# R603X.net
KiCad netlist of a schematic drawn in EAGLE
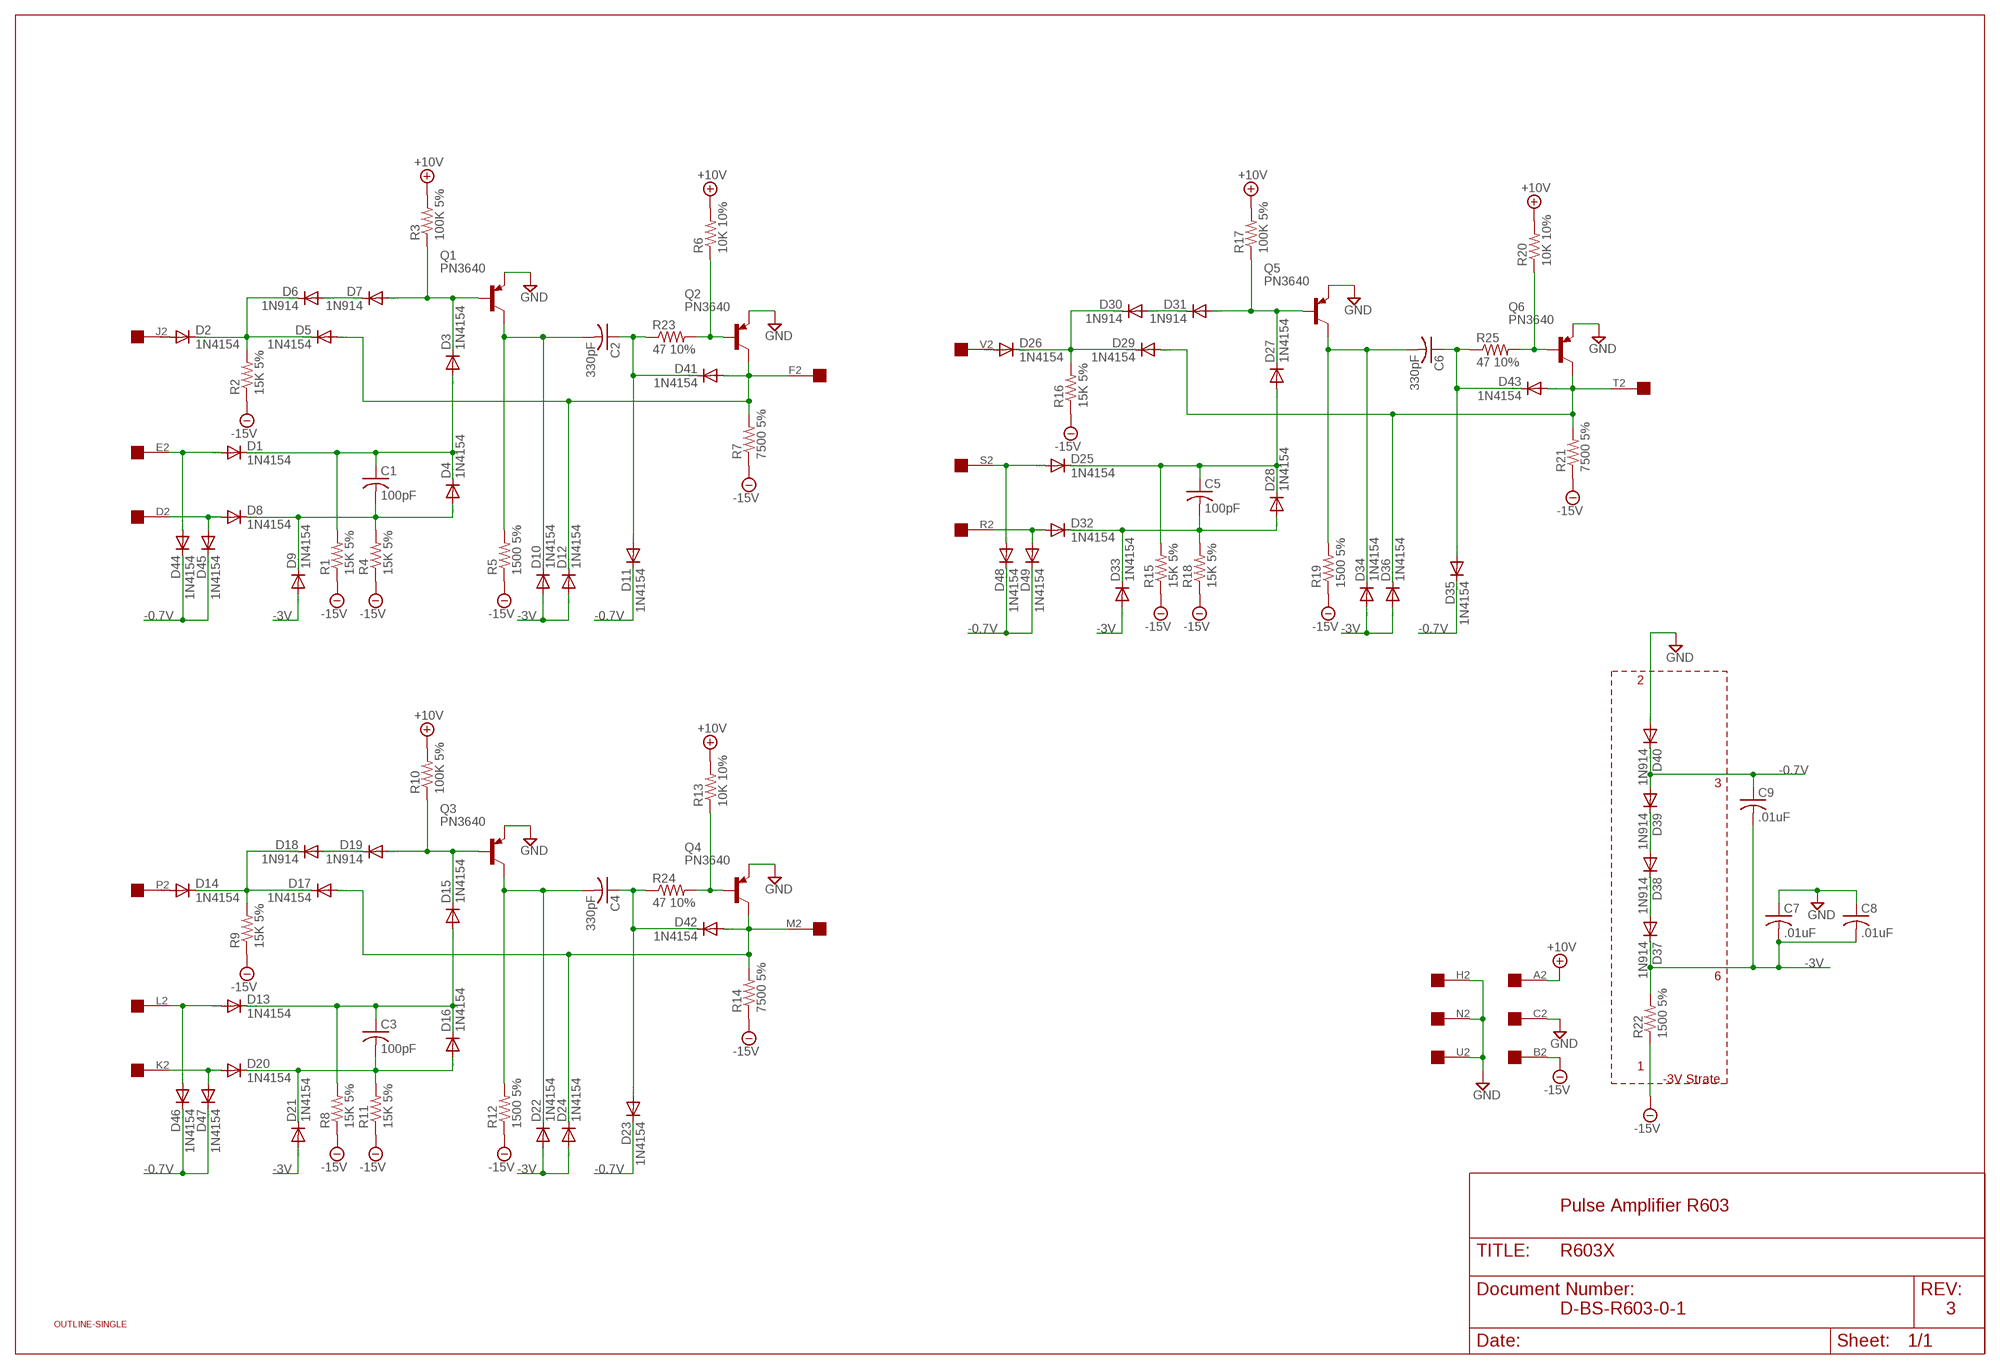
[diagram p0: schematic, sheet 1]

(export (version "E")
  (design (tool "Eeschema 10.0.6"))
  (components
    (comp (ref "C1")
      (value "100pF")
      (footprint "eagle-import:C050-025X075")
      (libsource (lib "eagle-import") (part "C-US050-025X075"))
    )
    (comp (ref "C2")
      (value "330pF")
      (footprint "eagle-import:C050-025X075")
      (libsource (lib "eagle-import") (part "C-US050-025X075"))
    )
    (comp (ref "C3")
      (value "100pF")
      (footprint "eagle-import:C050-025X075")
      (libsource (lib "eagle-import") (part "C-US050-025X075"))
    )
    (comp (ref "C4")
      (value "330pF")
      (footprint "eagle-import:C050-025X075")
      (libsource (lib "eagle-import") (part "C-US050-025X075"))
    )
    (comp (ref "C5")
      (value "100pF")
      (footprint "eagle-import:C050-025X075")
      (libsource (lib "eagle-import") (part "C-US050-025X075"))
    )
    (comp (ref "C6")
      (value "330pF")
      (footprint "eagle-import:C050-025X075")
      (libsource (lib "eagle-import") (part "C-US050-025X075"))
    )
    (comp (ref "C7")
      (value ".01uF")
      (footprint "eagle-import:C050-025X075")
      (libsource (lib "eagle-import") (part "C-US050-025X075"))
    )
    (comp (ref "C8")
      (value ".01uF")
      (footprint "eagle-import:C050-025X075")
      (libsource (lib "eagle-import") (part "C-US050-025X075"))
    )
    (comp (ref "C9")
      (value ".01uF")
      (footprint "eagle-import:C050-025X075")
      (libsource (lib "eagle-import") (part "C-US050-025X075"))
    )
    (comp (ref "D1")
      (value "1N4154")
      (footprint "eagle-import:DO35-10")
      (libsource (lib "eagle-import") (part "1N4148DO35-10"))
    )
    (comp (ref "D2")
      (value "1N4154")
      (footprint "eagle-import:DO35-10")
      (libsource (lib "eagle-import") (part "1N4148DO35-10"))
    )
    (comp (ref "D3")
      (value "1N4154")
      (footprint "eagle-import:DO35-10")
      (libsource (lib "eagle-import") (part "1N4148DO35-10"))
    )
    (comp (ref "D4")
      (value "1N4154")
      (footprint "eagle-import:DO35-10")
      (libsource (lib "eagle-import") (part "1N4148DO35-10"))
    )
    (comp (ref "D5")
      (value "1N4154")
      (footprint "eagle-import:DO35-10")
      (libsource (lib "eagle-import") (part "1N4148DO35-10"))
    )
    (comp (ref "D6")
      (value "1N914")
      (footprint "eagle-import:DO35-10")
      (libsource (lib "eagle-import") (part "1N4148DO35-10"))
    )
    (comp (ref "D7")
      (value "1N914")
      (footprint "eagle-import:DO35-10")
      (libsource (lib "eagle-import") (part "1N4148DO35-10"))
    )
    (comp (ref "D8")
      (value "1N4154")
      (footprint "eagle-import:DO35-10")
      (libsource (lib "eagle-import") (part "1N4148DO35-10"))
    )
    (comp (ref "D9")
      (value "1N4154")
      (footprint "eagle-import:DO35-10")
      (libsource (lib "eagle-import") (part "1N4148DO35-10"))
    )
    (comp (ref "D10")
      (value "1N4154")
      (footprint "eagle-import:DO35-10")
      (libsource (lib "eagle-import") (part "1N4148DO35-10"))
    )
    (comp (ref "D11")
      (value "1N4154")
      (footprint "eagle-import:DO35-10")
      (libsource (lib "eagle-import") (part "1N4148DO35-10"))
    )
    (comp (ref "D12")
      (value "1N4154")
      (footprint "eagle-import:DO35-10")
      (libsource (lib "eagle-import") (part "1N4148DO35-10"))
    )
    (comp (ref "D13")
      (value "1N4154")
      (footprint "eagle-import:DO35-10")
      (libsource (lib "eagle-import") (part "1N4148DO35-10"))
    )
    (comp (ref "D14")
      (value "1N4154")
      (footprint "eagle-import:DO35-10")
      (libsource (lib "eagle-import") (part "1N4148DO35-10"))
    )
    (comp (ref "D15")
      (value "1N4154")
      (footprint "eagle-import:DO35-10")
      (libsource (lib "eagle-import") (part "1N4148DO35-10"))
    )
    (comp (ref "D16")
      (value "1N4154")
      (footprint "eagle-import:DO35-10")
      (libsource (lib "eagle-import") (part "1N4148DO35-10"))
    )
    (comp (ref "D17")
      (value "1N4154")
      (footprint "eagle-import:DO35-10")
      (libsource (lib "eagle-import") (part "1N4148DO35-10"))
    )
    (comp (ref "D18")
      (value "1N914")
      (footprint "eagle-import:DO35-10")
      (libsource (lib "eagle-import") (part "1N4148DO35-10"))
    )
    (comp (ref "D19")
      (value "1N914")
      (footprint "eagle-import:DO35-10")
      (libsource (lib "eagle-import") (part "1N4148DO35-10"))
    )
    (comp (ref "D20")
      (value "1N4154")
      (footprint "eagle-import:DO35-10")
      (libsource (lib "eagle-import") (part "1N4148DO35-10"))
    )
    (comp (ref "D21")
      (value "1N4154")
      (footprint "eagle-import:DO35-10")
      (libsource (lib "eagle-import") (part "1N4148DO35-10"))
    )
    (comp (ref "D22")
      (value "1N4154")
      (footprint "eagle-import:DO35-10")
      (libsource (lib "eagle-import") (part "1N4148DO35-10"))
    )
    (comp (ref "D23")
      (value "1N4154")
      (footprint "eagle-import:DO35-10")
      (libsource (lib "eagle-import") (part "1N4148DO35-10"))
    )
    (comp (ref "D24")
      (value "1N4154")
      (footprint "eagle-import:DO35-10")
      (libsource (lib "eagle-import") (part "1N4148DO35-10"))
    )
    (comp (ref "D25")
      (value "1N4154")
      (footprint "eagle-import:DO35-10")
      (libsource (lib "eagle-import") (part "1N4148DO35-10"))
    )
    (comp (ref "D26")
      (value "1N4154")
      (footprint "eagle-import:DO35-10")
      (libsource (lib "eagle-import") (part "1N4148DO35-10"))
    )
    (comp (ref "D27")
      (value "1N4154")
      (footprint "eagle-import:DO35-10")
      (libsource (lib "eagle-import") (part "1N4148DO35-10"))
    )
    (comp (ref "D28")
      (value "1N4154")
      (footprint "eagle-import:DO35-10")
      (libsource (lib "eagle-import") (part "1N4148DO35-10"))
    )
    (comp (ref "D29")
      (value "1N4154")
      (footprint "eagle-import:DO35-10")
      (libsource (lib "eagle-import") (part "1N4148DO35-10"))
    )
    (comp (ref "D30")
      (value "1N914")
      (footprint "eagle-import:DO35-10")
      (libsource (lib "eagle-import") (part "1N4148DO35-10"))
    )
    (comp (ref "D31")
      (value "1N914")
      (footprint "eagle-import:DO35-10")
      (libsource (lib "eagle-import") (part "1N4148DO35-10"))
    )
    (comp (ref "D32")
      (value "1N4154")
      (footprint "eagle-import:DO35-10")
      (libsource (lib "eagle-import") (part "1N4148DO35-10"))
    )
    (comp (ref "D33")
      (value "1N4154")
      (footprint "eagle-import:DO35-10")
      (libsource (lib "eagle-import") (part "1N4148DO35-10"))
    )
    (comp (ref "D34")
      (value "1N4154")
      (footprint "eagle-import:DO35-10")
      (libsource (lib "eagle-import") (part "1N4148DO35-10"))
    )
    (comp (ref "D35")
      (value "1N4154")
      (footprint "eagle-import:DO35-10")
      (libsource (lib "eagle-import") (part "1N4148DO35-10"))
    )
    (comp (ref "D36")
      (value "1N4154")
      (footprint "eagle-import:DO35-10")
      (libsource (lib "eagle-import") (part "1N4148DO35-10"))
    )
    (comp (ref "D37")
      (value "1N914")
      (footprint "eagle-import:DO35-10")
      (libsource (lib "eagle-import") (part "1N4148DO35-10"))
    )
    (comp (ref "D38")
      (value "1N914")
      (footprint "eagle-import:DO35-10")
      (libsource (lib "eagle-import") (part "1N4148DO35-10"))
    )
    (comp (ref "D39")
      (value "1N914")
      (footprint "eagle-import:DO35-10")
      (libsource (lib "eagle-import") (part "1N4148DO35-10"))
    )
    (comp (ref "D40")
      (value "1N914")
      (footprint "eagle-import:DO35-10")
      (libsource (lib "eagle-import") (part "1N4148DO35-10"))
    )
    (comp (ref "D41")
      (value "1N4154")
      (footprint "eagle-import:DO35-10")
      (libsource (lib "eagle-import") (part "1N4148DO35-10"))
    )
    (comp (ref "D42")
      (value "1N4154")
      (footprint "eagle-import:DO35-10")
      (libsource (lib "eagle-import") (part "1N4148DO35-10"))
    )
    (comp (ref "D43")
      (value "1N4154")
      (footprint "eagle-import:DO35-10")
      (libsource (lib "eagle-import") (part "1N4148DO35-10"))
    )
    (comp (ref "D44")
      (value "1N4154")
      (footprint "eagle-import:DO35-10")
      (libsource (lib "eagle-import") (part "1N4148DO35-10"))
    )
    (comp (ref "D45")
      (value "1N4154")
      (footprint "eagle-import:DO35-10")
      (libsource (lib "eagle-import") (part "1N4148DO35-10"))
    )
    (comp (ref "D46")
      (value "1N4154")
      (footprint "eagle-import:DO35-10")
      (libsource (lib "eagle-import") (part "1N4148DO35-10"))
    )
    (comp (ref "D47")
      (value "1N4154")
      (footprint "eagle-import:DO35-10")
      (libsource (lib "eagle-import") (part "1N4148DO35-10"))
    )
    (comp (ref "D48")
      (value "1N4154")
      (footprint "eagle-import:DO35-10")
      (libsource (lib "eagle-import") (part "1N4148DO35-10"))
    )
    (comp (ref "D49")
      (value "1N4154")
      (footprint "eagle-import:DO35-10")
      (libsource (lib "eagle-import") (part "1N4148DO35-10"))
    )
    (comp (ref "Q1")
      (value "PN3640")
      (footprint "eagle-import:TO39")
      (libsource (lib "eagle-import") (part "2N2904"))
    )
    (comp (ref "Q2")
      (value "PN3640")
      (footprint "eagle-import:TO39")
      (libsource (lib "eagle-import") (part "2N2904"))
    )
    (comp (ref "Q3")
      (value "PN3640")
      (footprint "eagle-import:TO39")
      (libsource (lib "eagle-import") (part "2N2904"))
    )
    (comp (ref "Q4")
      (value "PN3640")
      (footprint "eagle-import:TO39")
      (libsource (lib "eagle-import") (part "2N2904"))
    )
    (comp (ref "Q5")
      (value "PN3640")
      (footprint "eagle-import:TO39")
      (libsource (lib "eagle-import") (part "2N2904"))
    )
    (comp (ref "Q6")
      (value "PN3640")
      (footprint "eagle-import:TO39")
      (libsource (lib "eagle-import") (part "2N2904"))
    )
    (comp (ref "R1")
      (value "15K 5%")
      (footprint "eagle-import:0207_10")
      (libsource (lib "eagle-import") (part "R-US_0207/10"))
    )
    (comp (ref "R2")
      (value "15K 5%")
      (footprint "eagle-import:0207_10")
      (libsource (lib "eagle-import") (part "R-US_0207/10"))
    )
    (comp (ref "R3")
      (value "100K 5%")
      (footprint "eagle-import:0207_10")
      (libsource (lib "eagle-import") (part "R-US_0207/10"))
    )
    (comp (ref "R4")
      (value "15K 5%")
      (footprint "eagle-import:0207_10")
      (libsource (lib "eagle-import") (part "R-US_0207/10"))
    )
    (comp (ref "R5")
      (value "1500 5%")
      (footprint "eagle-import:0207_10")
      (libsource (lib "eagle-import") (part "R-US_0207/10"))
    )
    (comp (ref "R6")
      (value "10K 10%")
      (footprint "eagle-import:0207_10")
      (libsource (lib "eagle-import") (part "R-US_0207/10"))
    )
    (comp (ref "R7")
      (value "7500 5%")
      (footprint "eagle-import:0207_10")
      (libsource (lib "eagle-import") (part "R-US_0207/10"))
    )
    (comp (ref "R8")
      (value "15K 5%")
      (footprint "eagle-import:0207_10")
      (libsource (lib "eagle-import") (part "R-US_0207/10"))
    )
    (comp (ref "R9")
      (value "15K 5%")
      (footprint "eagle-import:0207_10")
      (libsource (lib "eagle-import") (part "R-US_0207/10"))
    )
    (comp (ref "R10")
      (value "100K 5%")
      (footprint "eagle-import:0207_10")
      (libsource (lib "eagle-import") (part "R-US_0207/10"))
    )
    (comp (ref "R11")
      (value "15K 5%")
      (footprint "eagle-import:0207_10")
      (libsource (lib "eagle-import") (part "R-US_0207/10"))
    )
    (comp (ref "R12")
      (value "1500 5%")
      (footprint "eagle-import:0207_10")
      (libsource (lib "eagle-import") (part "R-US_0207/10"))
    )
    (comp (ref "R13")
      (value "10K 10%")
      (footprint "eagle-import:0207_10")
      (libsource (lib "eagle-import") (part "R-US_0207/10"))
    )
    (comp (ref "R14")
      (value "7500 5%")
      (footprint "eagle-import:0207_10")
      (libsource (lib "eagle-import") (part "R-US_0207/10"))
    )
    (comp (ref "R15")
      (value "15K 5%")
      (footprint "eagle-import:0207_10")
      (libsource (lib "eagle-import") (part "R-US_0207/10"))
    )
    (comp (ref "R16")
      (value "15K 5%")
      (footprint "eagle-import:0207_10")
      (libsource (lib "eagle-import") (part "R-US_0207/10"))
    )
    (comp (ref "R17")
      (value "100K 5%")
      (footprint "eagle-import:0207_10")
      (libsource (lib "eagle-import") (part "R-US_0207/10"))
    )
    (comp (ref "R18")
      (value "15K 5%")
      (footprint "eagle-import:0207_10")
      (libsource (lib "eagle-import") (part "R-US_0207/10"))
    )
    (comp (ref "R19")
      (value "1500 5%")
      (footprint "eagle-import:0207_10")
      (libsource (lib "eagle-import") (part "R-US_0207/10"))
    )
    (comp (ref "R20")
      (value "10K 10%")
      (footprint "eagle-import:0207_10")
      (libsource (lib "eagle-import") (part "R-US_0207/10"))
    )
    (comp (ref "R21")
      (value "7500 5%")
      (footprint "eagle-import:0207_10")
      (libsource (lib "eagle-import") (part "R-US_0207/10"))
    )
    (comp (ref "R22")
      (value "1500 5%")
      (footprint "eagle-import:0207_10")
      (libsource (lib "eagle-import") (part "R-US_0207/10"))
    )
    (comp (ref "R23")
      (value "47 10%")
      (footprint "eagle-import:0207_10")
      (libsource (lib "eagle-import") (part "R-US_0207/10"))
    )
    (comp (ref "R24")
      (value "47 10%")
      (footprint "eagle-import:0207_10")
      (libsource (lib "eagle-import") (part "R-US_0207/10"))
    )
    (comp (ref "R25")
      (value "47 10%")
      (footprint "eagle-import:0207_10")
      (libsource (lib "eagle-import") (part "R-US_0207/10"))
    )
    (comp (ref "U$1")
      (value "OUTLINE-SINGLE")
      (footprint "eagle-import:SINGLE")
      (libsource (lib "eagle-import") (part "OUTLINE-SINGLE"))
    )
    (comp (ref "U$2")
      (value "EDGE-1")
      (footprint "eagle-import:EDGE-CON1")
      (libsource (lib "eagle-import") (part "EDGE-1"))
    )
  )
  (nets
    (net (code "1") (name "+10V") (class "Default")
      (node (ref "R10") (pin "2") (pinfunction "2_2") (pintype "passive"))
      (node (ref "R13") (pin "2") (pinfunction "2_2") (pintype "passive"))
      (node (ref "R17") (pin "2") (pinfunction "2_2") (pintype "passive"))
      (node (ref "R20") (pin "2") (pinfunction "2_2") (pintype "passive"))
      (node (ref "R3") (pin "2") (pinfunction "2_2") (pintype "passive"))
      (node (ref "R6") (pin "2") (pinfunction "2_2") (pintype "passive"))
      (node (ref "U$2") (pin "A2") (pinfunction "1_A2") (pintype "bidirectional"))
    )
    (net (code "2") (name "-15V") (class "Default")
      (node (ref "R1") (pin "1") (pinfunction "1_1") (pintype "passive"))
      (node (ref "R11") (pin "1") (pinfunction "1_1") (pintype "passive"))
      (node (ref "R12") (pin "1") (pinfunction "1_1") (pintype "passive"))
      (node (ref "R14") (pin "1") (pinfunction "1_1") (pintype "passive"))
      (node (ref "R15") (pin "1") (pinfunction "1_1") (pintype "passive"))
      (node (ref "R16") (pin "1") (pinfunction "1_1") (pintype "passive"))
      (node (ref "R18") (pin "1") (pinfunction "1_1") (pintype "passive"))
      (node (ref "R19") (pin "1") (pinfunction "1_1") (pintype "passive"))
      (node (ref "R2") (pin "1") (pinfunction "1_1") (pintype "passive"))
      (node (ref "R21") (pin "1") (pinfunction "1_1") (pintype "passive"))
      (node (ref "R22") (pin "1") (pinfunction "1_1") (pintype "passive"))
      (node (ref "R4") (pin "1") (pinfunction "1_1") (pintype "passive"))
      (node (ref "R5") (pin "1") (pinfunction "1_1") (pintype "passive"))
      (node (ref "R7") (pin "1") (pinfunction "1_1") (pintype "passive"))
      (node (ref "R8") (pin "1") (pinfunction "1_1") (pintype "passive"))
      (node (ref "R9") (pin "1") (pinfunction "1_1") (pintype "passive"))
      (node (ref "U$2") (pin "B2") (pinfunction "1_B2") (pintype "bidirectional"))
    )
    (net (code "3") (name "/-0.7V") (class "Default")
      (node (ref "C9") (pin "1") (pinfunction "1_1") (pintype "passive"))
      (node (ref "D11") (pin "C") (pinfunction "C_C") (pintype "passive"))
      (node (ref "D23") (pin "C") (pinfunction "C_C") (pintype "passive"))
      (node (ref "D35") (pin "C") (pinfunction "C_C") (pintype "passive"))
      (node (ref "D39") (pin "A") (pinfunction "A_A") (pintype "passive"))
      (node (ref "D40") (pin "C") (pinfunction "C_C") (pintype "passive"))
      (node (ref "D44") (pin "C") (pinfunction "C_C") (pintype "passive"))
      (node (ref "D45") (pin "C") (pinfunction "C_C") (pintype "passive"))
      (node (ref "D46") (pin "C") (pinfunction "C_C") (pintype "passive"))
      (node (ref "D47") (pin "C") (pinfunction "C_C") (pintype "passive"))
      (node (ref "D48") (pin "C") (pinfunction "C_C") (pintype "passive"))
      (node (ref "D49") (pin "C") (pinfunction "C_C") (pintype "passive"))
    )
    (net (code "4") (name "/-3V") (class "Default")
      (node (ref "C7") (pin "2") (pinfunction "2_2") (pintype "passive"))
      (node (ref "C8") (pin "2") (pinfunction "2_2") (pintype "passive"))
      (node (ref "C9") (pin "2") (pinfunction "2_2") (pintype "passive"))
      (node (ref "D10") (pin "A") (pinfunction "A_A") (pintype "passive"))
      (node (ref "D12") (pin "A") (pinfunction "A_A") (pintype "passive"))
      (node (ref "D21") (pin "A") (pinfunction "A_A") (pintype "passive"))
      (node (ref "D22") (pin "A") (pinfunction "A_A") (pintype "passive"))
      (node (ref "D24") (pin "A") (pinfunction "A_A") (pintype "passive"))
      (node (ref "D33") (pin "A") (pinfunction "A_A") (pintype "passive"))
      (node (ref "D34") (pin "A") (pinfunction "A_A") (pintype "passive"))
      (node (ref "D36") (pin "A") (pinfunction "A_A") (pintype "passive"))
      (node (ref "D37") (pin "C") (pinfunction "C_C") (pintype "passive"))
      (node (ref "D9") (pin "A") (pinfunction "A_A") (pintype "passive"))
      (node (ref "R22") (pin "2") (pinfunction "2_2") (pintype "passive"))
    )
    (net (code "5") (name "GND") (class "Default")
      (node (ref "C7") (pin "1") (pinfunction "1_1") (pintype "passive"))
      (node (ref "C8") (pin "1") (pinfunction "1_1") (pintype "passive"))
      (node (ref "D40") (pin "A") (pinfunction "A_A") (pintype "passive"))
      (node (ref "Q1") (pin "1") (pinfunction "E_1") (pintype "passive"))
      (node (ref "Q2") (pin "1") (pinfunction "E_1") (pintype "passive"))
      (node (ref "Q3") (pin "1") (pinfunction "E_1") (pintype "passive"))
      (node (ref "Q4") (pin "1") (pinfunction "E_1") (pintype "passive"))
      (node (ref "Q5") (pin "1") (pinfunction "E_1") (pintype "passive"))
      (node (ref "Q6") (pin "1") (pinfunction "E_1") (pintype "passive"))
      (node (ref "U$2") (pin "C2") (pinfunction "1_C2") (pintype "bidirectional"))
      (node (ref "U$2") (pin "H2") (pinfunction "1_H2") (pintype "bidirectional"))
      (node (ref "U$2") (pin "N2") (pinfunction "1_N2") (pintype "bidirectional"))
      (node (ref "U$2") (pin "U2") (pinfunction "1_U2") (pintype "bidirectional"))
    )
    (net (code "6") (name "Net-(C1-Pad1)") (class "Default")
      (node (ref "C1") (pin "1") (pinfunction "1_1") (pintype "passive"))
      (node (ref "D1") (pin "C") (pinfunction "C_C") (pintype "passive"))
      (node (ref "D3") (pin "A") (pinfunction "A_A") (pintype "passive"))
      (node (ref "D4") (pin "C") (pinfunction "C_C") (pintype "passive"))
      (node (ref "R1") (pin "2") (pinfunction "2_2") (pintype "passive"))
    )
    (net (code "7") (name "Net-(C1-Pad2)") (class "Default")
      (node (ref "C1") (pin "2") (pinfunction "2_2") (pintype "passive"))
      (node (ref "D4") (pin "A") (pinfunction "A_A") (pintype "passive"))
      (node (ref "D8") (pin "C") (pinfunction "C_C") (pintype "passive"))
      (node (ref "D9") (pin "C") (pinfunction "C_C") (pintype "passive"))
      (node (ref "R4") (pin "2") (pinfunction "2_2") (pintype "passive"))
    )
    (net (code "8") (name "Net-(C2-Pad1)") (class "Default")
      (node (ref "C2") (pin "1") (pinfunction "1_1") (pintype "passive"))
      (node (ref "D11") (pin "A") (pinfunction "A_A") (pintype "passive"))
      (node (ref "D41") (pin "C") (pinfunction "C_C") (pintype "passive"))
      (node (ref "R23") (pin "1") (pinfunction "1_1") (pintype "passive"))
    )
    (net (code "9") (name "Net-(C3-Pad1)") (class "Default")
      (node (ref "C3") (pin "1") (pinfunction "1_1") (pintype "passive"))
      (node (ref "D13") (pin "C") (pinfunction "C_C") (pintype "passive"))
      (node (ref "D15") (pin "A") (pinfunction "A_A") (pintype "passive"))
      (node (ref "D16") (pin "C") (pinfunction "C_C") (pintype "passive"))
      (node (ref "R8") (pin "2") (pinfunction "2_2") (pintype "passive"))
    )
    (net (code "10") (name "Net-(C3-Pad2)") (class "Default")
      (node (ref "C3") (pin "2") (pinfunction "2_2") (pintype "passive"))
      (node (ref "D16") (pin "A") (pinfunction "A_A") (pintype "passive"))
      (node (ref "D20") (pin "C") (pinfunction "C_C") (pintype "passive"))
      (node (ref "D21") (pin "C") (pinfunction "C_C") (pintype "passive"))
      (node (ref "R11") (pin "2") (pinfunction "2_2") (pintype "passive"))
    )
    (net (code "11") (name "Net-(C4-Pad1)") (class "Default")
      (node (ref "C4") (pin "1") (pinfunction "1_1") (pintype "passive"))
      (node (ref "D23") (pin "A") (pinfunction "A_A") (pintype "passive"))
      (node (ref "D42") (pin "C") (pinfunction "C_C") (pintype "passive"))
      (node (ref "R24") (pin "1") (pinfunction "1_1") (pintype "passive"))
    )
    (net (code "12") (name "Net-(C5-Pad1)") (class "Default")
      (node (ref "C5") (pin "1") (pinfunction "1_1") (pintype "passive"))
      (node (ref "D25") (pin "C") (pinfunction "C_C") (pintype "passive"))
      (node (ref "D27") (pin "A") (pinfunction "A_A") (pintype "passive"))
      (node (ref "D28") (pin "C") (pinfunction "C_C") (pintype "passive"))
      (node (ref "R15") (pin "2") (pinfunction "2_2") (pintype "passive"))
    )
    (net (code "13") (name "Net-(C5-Pad2)") (class "Default")
      (node (ref "C5") (pin "2") (pinfunction "2_2") (pintype "passive"))
      (node (ref "D28") (pin "A") (pinfunction "A_A") (pintype "passive"))
      (node (ref "D32") (pin "C") (pinfunction "C_C") (pintype "passive"))
      (node (ref "D33") (pin "C") (pinfunction "C_C") (pintype "passive"))
      (node (ref "R18") (pin "2") (pinfunction "2_2") (pintype "passive"))
    )
    (net (code "14") (name "Net-(C6-Pad1)") (class "Default")
      (node (ref "C6") (pin "1") (pinfunction "1_1") (pintype "passive"))
      (node (ref "D35") (pin "A") (pinfunction "A_A") (pintype "passive"))
      (node (ref "D43") (pin "C") (pinfunction "C_C") (pintype "passive"))
      (node (ref "R25") (pin "1") (pinfunction "1_1") (pintype "passive"))
    )
    (net (code "15") (name "Net-(D2-PadC)") (class "Default")
      (node (ref "D2") (pin "C") (pinfunction "C_C") (pintype "passive"))
      (node (ref "D5") (pin "C") (pinfunction "C_C") (pintype "passive"))
      (node (ref "D6") (pin "C") (pinfunction "C_C") (pintype "passive"))
      (node (ref "R2") (pin "2") (pinfunction "2_2") (pintype "passive"))
    )
    (net (code "16") (name "Net-(D6-PadA)") (class "Default")
      (node (ref "D6") (pin "A") (pinfunction "A_A") (pintype "passive"))
      (node (ref "D7") (pin "C") (pinfunction "C_C") (pintype "passive"))
    )
    (net (code "17") (name "Net-(D14-PadC)") (class "Default")
      (node (ref "D14") (pin "C") (pinfunction "C_C") (pintype "passive"))
      (node (ref "D17") (pin "C") (pinfunction "C_C") (pintype "passive"))
      (node (ref "D18") (pin "C") (pinfunction "C_C") (pintype "passive"))
      (node (ref "R9") (pin "2") (pinfunction "2_2") (pintype "passive"))
    )
    (net (code "18") (name "Net-(D18-PadA)") (class "Default")
      (node (ref "D18") (pin "A") (pinfunction "A_A") (pintype "passive"))
      (node (ref "D19") (pin "C") (pinfunction "C_C") (pintype "passive"))
    )
    (net (code "19") (name "Net-(D26-PadC)") (class "Default")
      (node (ref "D26") (pin "C") (pinfunction "C_C") (pintype "passive"))
      (node (ref "D29") (pin "C") (pinfunction "C_C") (pintype "passive"))
      (node (ref "D30") (pin "C") (pinfunction "C_C") (pintype "passive"))
      (node (ref "R16") (pin "2") (pinfunction "2_2") (pintype "passive"))
    )
    (net (code "20") (name "Net-(D30-PadA)") (class "Default")
      (node (ref "D30") (pin "A") (pinfunction "A_A") (pintype "passive"))
      (node (ref "D31") (pin "C") (pinfunction "C_C") (pintype "passive"))
    )
    (net (code "21") (name "Net-(D37-PadA)") (class "Default")
      (node (ref "D37") (pin "A") (pinfunction "A_A") (pintype "passive"))
      (node (ref "D38") (pin "C") (pinfunction "C_C") (pintype "passive"))
    )
    (net (code "22") (name "Net-(D38-PadA)") (class "Default")
      (node (ref "D38") (pin "A") (pinfunction "A_A") (pintype "passive"))
      (node (ref "D39") (pin "C") (pinfunction "C_C") (pintype "passive"))
    )
    (net (code "23") (name "Net-(Q1-B)") (class "Default")
      (node (ref "D3") (pin "C") (pinfunction "C_C") (pintype "passive"))
      (node (ref "D7") (pin "A") (pinfunction "A_A") (pintype "passive"))
      (node (ref "Q1") (pin "2") (pinfunction "B_2") (pintype "passive"))
      (node (ref "R3") (pin "1") (pinfunction "1_1") (pintype "passive"))
    )
    (net (code "24") (name "Net-(Q1-C)") (class "Default")
      (node (ref "C2") (pin "2") (pinfunction "2_2") (pintype "passive"))
      (node (ref "D10") (pin "C") (pinfunction "C_C") (pintype "passive"))
      (node (ref "Q1") (pin "3") (pinfunction "C_3") (pintype "passive"))
      (node (ref "R5") (pin "2") (pinfunction "2_2") (pintype "passive"))
    )
    (net (code "25") (name "Net-(Q2-B)") (class "Default")
      (node (ref "Q2") (pin "2") (pinfunction "B_2") (pintype "passive"))
      (node (ref "R23") (pin "2") (pinfunction "2_2") (pintype "passive"))
      (node (ref "R6") (pin "1") (pinfunction "1_1") (pintype "passive"))
    )
    (net (code "26") (name "Net-(Q2-C)") (class "Default")
      (node (ref "D12") (pin "C") (pinfunction "C_C") (pintype "passive"))
      (node (ref "D41") (pin "A") (pinfunction "A_A") (pintype "passive"))
      (node (ref "D5") (pin "A") (pinfunction "A_A") (pintype "passive"))
      (node (ref "Q2") (pin "3") (pinfunction "C_3") (pintype "passive"))
      (node (ref "R7") (pin "2") (pinfunction "2_2") (pintype "passive"))
      (node (ref "U$2") (pin "F2") (pinfunction "1_F2") (pintype "bidirectional"))
    )
    (net (code "27") (name "Net-(Q3-B)") (class "Default")
      (node (ref "D15") (pin "C") (pinfunction "C_C") (pintype "passive"))
      (node (ref "D19") (pin "A") (pinfunction "A_A") (pintype "passive"))
      (node (ref "Q3") (pin "2") (pinfunction "B_2") (pintype "passive"))
      (node (ref "R10") (pin "1") (pinfunction "1_1") (pintype "passive"))
    )
    (net (code "28") (name "Net-(Q3-C)") (class "Default")
      (node (ref "C4") (pin "2") (pinfunction "2_2") (pintype "passive"))
      (node (ref "D22") (pin "C") (pinfunction "C_C") (pintype "passive"))
      (node (ref "Q3") (pin "3") (pinfunction "C_3") (pintype "passive"))
      (node (ref "R12") (pin "2") (pinfunction "2_2") (pintype "passive"))
    )
    (net (code "29") (name "Net-(Q4-B)") (class "Default")
      (node (ref "Q4") (pin "2") (pinfunction "B_2") (pintype "passive"))
      (node (ref "R13") (pin "1") (pinfunction "1_1") (pintype "passive"))
      (node (ref "R24") (pin "2") (pinfunction "2_2") (pintype "passive"))
    )
    (net (code "30") (name "Net-(Q4-C)") (class "Default")
      (node (ref "D17") (pin "A") (pinfunction "A_A") (pintype "passive"))
      (node (ref "D24") (pin "C") (pinfunction "C_C") (pintype "passive"))
      (node (ref "D42") (pin "A") (pinfunction "A_A") (pintype "passive"))
      (node (ref "Q4") (pin "3") (pinfunction "C_3") (pintype "passive"))
      (node (ref "R14") (pin "2") (pinfunction "2_2") (pintype "passive"))
      (node (ref "U$2") (pin "M2") (pinfunction "1_M2") (pintype "bidirectional"))
    )
    (net (code "31") (name "Net-(Q5-B)") (class "Default")
      (node (ref "D27") (pin "C") (pinfunction "C_C") (pintype "passive"))
      (node (ref "D31") (pin "A") (pinfunction "A_A") (pintype "passive"))
      (node (ref "Q5") (pin "2") (pinfunction "B_2") (pintype "passive"))
      (node (ref "R17") (pin "1") (pinfunction "1_1") (pintype "passive"))
    )
    (net (code "32") (name "Net-(Q5-C)") (class "Default")
      (node (ref "C6") (pin "2") (pinfunction "2_2") (pintype "passive"))
      (node (ref "D34") (pin "C") (pinfunction "C_C") (pintype "passive"))
      (node (ref "Q5") (pin "3") (pinfunction "C_3") (pintype "passive"))
      (node (ref "R19") (pin "2") (pinfunction "2_2") (pintype "passive"))
    )
    (net (code "33") (name "Net-(Q6-B)") (class "Default")
      (node (ref "Q6") (pin "2") (pinfunction "B_2") (pintype "passive"))
      (node (ref "R20") (pin "1") (pinfunction "1_1") (pintype "passive"))
      (node (ref "R25") (pin "2") (pinfunction "2_2") (pintype "passive"))
    )
    (net (code "34") (name "Net-(Q6-C)") (class "Default")
      (node (ref "D29") (pin "A") (pinfunction "A_A") (pintype "passive"))
      (node (ref "D36") (pin "C") (pinfunction "C_C") (pintype "passive"))
      (node (ref "D43") (pin "A") (pinfunction "A_A") (pintype "passive"))
      (node (ref "Q6") (pin "3") (pinfunction "C_3") (pintype "passive"))
      (node (ref "R21") (pin "2") (pinfunction "2_2") (pintype "passive"))
      (node (ref "U$2") (pin "T2") (pinfunction "1_T2") (pintype "bidirectional"))
    )
    (net (code "35") (name "Net-(U$2D-1)") (class "Default")
      (node (ref "D45") (pin "A") (pinfunction "A_A") (pintype "passive"))
      (node (ref "D8") (pin "A") (pinfunction "A_A") (pintype "passive"))
      (node (ref "U$2") (pin "D2") (pinfunction "1_D2") (pintype "bidirectional"))
    )
    (net (code "36") (name "Net-(U$2E-1)") (class "Default")
      (node (ref "D1") (pin "A") (pinfunction "A_A") (pintype "passive"))
      (node (ref "D44") (pin "A") (pinfunction "A_A") (pintype "passive"))
      (node (ref "U$2") (pin "E2") (pinfunction "1_E2") (pintype "bidirectional"))
    )
    (net (code "37") (name "Net-(U$2H-1)") (class "Default")
      (node (ref "D2") (pin "A") (pinfunction "A_A") (pintype "passive"))
      (node (ref "U$2") (pin "J2") (pinfunction "1_J2") (pintype "bidirectional"))
    )
    (net (code "38") (name "Net-(U$2I-1)") (class "Default")
      (node (ref "D20") (pin "A") (pinfunction "A_A") (pintype "passive"))
      (node (ref "D47") (pin "A") (pinfunction "A_A") (pintype "passive"))
      (node (ref "U$2") (pin "K2") (pinfunction "1_K2") (pintype "bidirectional"))
    )
    (net (code "39") (name "Net-(U$2J-1)") (class "Default")
      (node (ref "D13") (pin "A") (pinfunction "A_A") (pintype "passive"))
      (node (ref "D46") (pin "A") (pinfunction "A_A") (pintype "passive"))
      (node (ref "U$2") (pin "L2") (pinfunction "1_L2") (pintype "bidirectional"))
    )
    (net (code "40") (name "Net-(U$2M-1)") (class "Default")
      (node (ref "D14") (pin "A") (pinfunction "A_A") (pintype "passive"))
      (node (ref "U$2") (pin "P2") (pinfunction "1_P2") (pintype "bidirectional"))
    )
    (net (code "41") (name "Net-(U$2N-1)") (class "Default")
      (node (ref "D32") (pin "A") (pinfunction "A_A") (pintype "passive"))
      (node (ref "D49") (pin "A") (pinfunction "A_A") (pintype "passive"))
      (node (ref "U$2") (pin "R2") (pinfunction "1_R2") (pintype "bidirectional"))
    )
    (net (code "42") (name "Net-(U$2O-1)") (class "Default")
      (node (ref "D25") (pin "A") (pinfunction "A_A") (pintype "passive"))
      (node (ref "D48") (pin "A") (pinfunction "A_A") (pintype "passive"))
      (node (ref "U$2") (pin "S2") (pinfunction "1_S2") (pintype "bidirectional"))
    )
    (net (code "43") (name "Net-(U$2R-1)") (class "Default")
      (node (ref "D26") (pin "A") (pinfunction "A_A") (pintype "passive"))
      (node (ref "U$2") (pin "V2") (pinfunction "1_V2") (pintype "bidirectional"))
    )
  )
)
